# Sound.net
KiCad netlist of a schematic drawn in Altium Designer
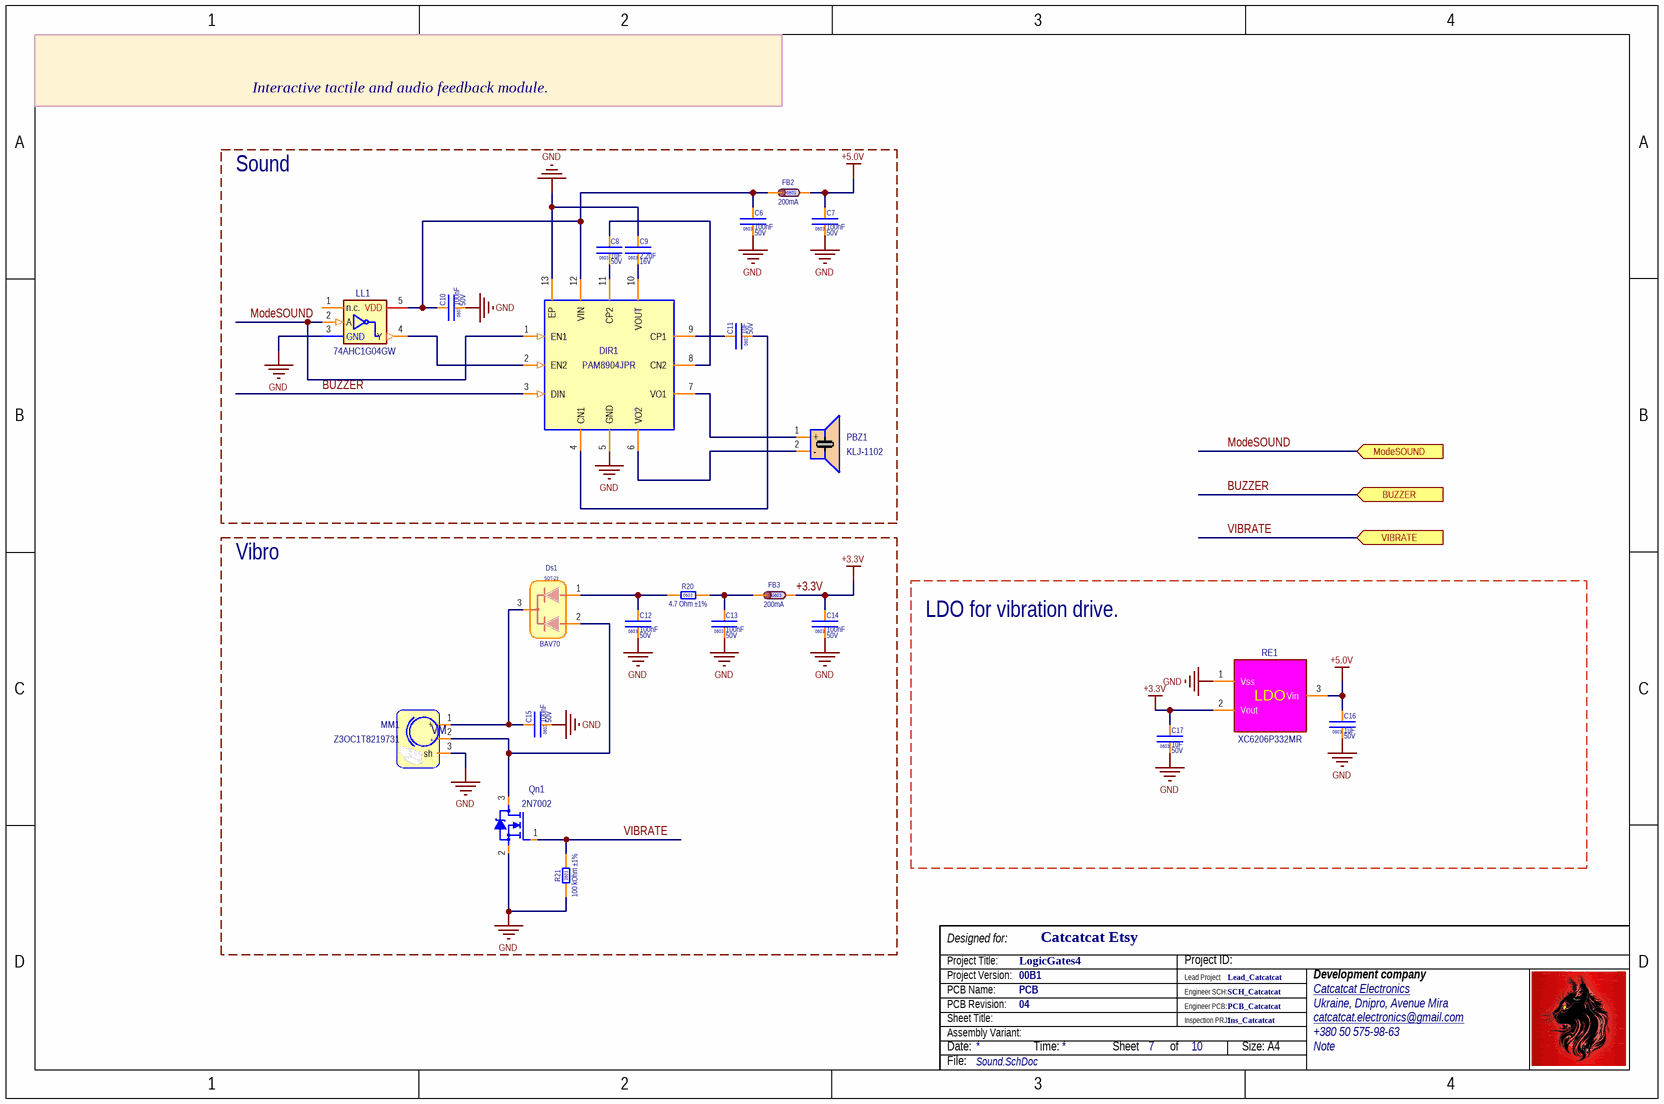
[diagram p0: Sound.SchDoc]

(export (version "E")
  (design (tool "Eeschema 10.0.6"))
  (components
    (comp (ref "C6")
      (value "100nF")
      (footprint "CC0603(1608)x0.8")
      (description "100 nF ±10% 50V X7R")
      (fields
        (field (name "TOLERANCE") "±10%")
        (field (name "VOLTAGE") "50V")
        (field (name "Comment") "100 nF ±10% 50V")
        (field (name "PUBLISHER") "Catcatcat Electronics")
      )
      (libsource (lib "IPC-7351chipCAPC") (part "0603 0.1 uF (B)"))
    )
    (comp (ref "C7")
      (value "100nF")
      (footprint "CC0603(1608)x0.8")
      (description "100 nF ±10% 50V X7R")
      (fields
        (field (name "TOLERANCE") "±10%")
        (field (name "VOLTAGE") "50V")
        (field (name "Comment") "100 nF ±10% 50V")
        (field (name "PUBLISHER") "Catcatcat Electronics")
      )
      (libsource (lib "IPC-7351chipCAPC") (part "0603 0.1 uF (B)"))
    )
    (comp (ref "C8")
      (value "1uF")
      (footprint "CC0603(1608)x0.8")
      (description "1.0 uF ±10% 50V X5R")
      (fields
        (field (name "TOLERANCE") "±10%")
        (field (name "VOLTAGE") "50V")
        (field (name "Comment") "1uF ±10% 50V 0603")
        (field (name "PUBLISHER") "Catcatcat Electronics")
      )
      (libsource (lib "IPC-7351chipCAPC") (part "0603 1.0 uF 50V (B)"))
    )
    (comp (ref "C9")
      (value "2.2uF")
      (footprint "CC0603(1608)x0.8")
      (description "2.2 uF ±10% 16V X5R")
      (fields
        (field (name "TOLERANCE") "±10%")
        (field (name "VOLTAGE") "16V")
        (field (name "Comment") "2.2uF ±10% 16V 0603")
        (field (name "PUBLISHER") "Catcatcat Electronics")
      )
      (libsource (lib "IPC-7351chipCAPC") (part "0603 2.2 uF 16V (B)"))
    )
    (comp (ref "C10")
      (value "100nF")
      (footprint "CC0603(1608)x0.8")
      (description "100 nF ±10% 50V X7R")
      (fields
        (field (name "TOLERANCE") "±10%")
        (field (name "VOLTAGE") "50V")
        (field (name "Comment") "100 nF ±10% 50V")
        (field (name "PUBLISHER") "Catcatcat Electronics")
      )
      (libsource (lib "IPC-7351chipCAPC") (part "0603 0.1 uF (B)"))
    )
    (comp (ref "C11")
      (value "1uF")
      (footprint "CC0603(1608)x0.8")
      (description "1.0 uF ±10% 50V X5R")
      (fields
        (field (name "TOLERANCE") "±10%")
        (field (name "VOLTAGE") "50V")
        (field (name "Comment") "1uF ±10% 50V 0603")
        (field (name "PUBLISHER") "Catcatcat Electronics")
      )
      (libsource (lib "IPC-7351chipCAPC") (part "0603 1.0 uF 50V (B)"))
    )
    (comp (ref "C12")
      (value "100nF")
      (footprint "CC0603(1608)x0.8")
      (description "100 nF ±10% 50V X7R")
      (fields
        (field (name "TOLERANCE") "±10%")
        (field (name "VOLTAGE") "50V")
        (field (name "Comment") "100 nF ±10% 50V")
        (field (name "PUBLISHER") "Catcatcat Electronics")
      )
      (libsource (lib "IPC-7351chipCAPC") (part "0603 0.1 uF (B)"))
    )
    (comp (ref "C13")
      (value "100nF")
      (footprint "CC0603(1608)x0.8")
      (description "100 nF ±10% 50V X7R")
      (fields
        (field (name "TOLERANCE") "±10%")
        (field (name "VOLTAGE") "50V")
        (field (name "Comment") "100 nF ±10% 50V")
        (field (name "PUBLISHER") "Catcatcat Electronics")
      )
      (libsource (lib "IPC-7351chipCAPC") (part "0603 0.1 uF (B)"))
    )
    (comp (ref "C14")
      (value "100nF")
      (footprint "CC0603(1608)x0.8")
      (description "100 nF ±10% 50V X7R")
      (fields
        (field (name "TOLERANCE") "±10%")
        (field (name "VOLTAGE") "50V")
        (field (name "Comment") "100 nF ±10% 50V")
        (field (name "PUBLISHER") "Catcatcat Electronics")
      )
      (libsource (lib "IPC-7351chipCAPC") (part "0603 0.1 uF (B)"))
    )
    (comp (ref "C15")
      (value "100nF")
      (footprint "CC0603(1608)x0.8")
      (description "100 nF ±10% 50V X7R")
      (fields
        (field (name "TOLERANCE") "±10%")
        (field (name "VOLTAGE") "50V")
        (field (name "Comment") "100 nF ±10% 50V")
        (field (name "PUBLISHER") "Catcatcat Electronics")
      )
      (libsource (lib "IPC-7351chipCAPC") (part "0603 0.1 uF (B)"))
    )
    (comp (ref "C16")
      (value "1uF")
      (footprint "CC0603(1608)x0.8")
      (description "1.0 uF ±10% 50V X5R")
      (fields
        (field (name "TOLERANCE") "±10%")
        (field (name "VOLTAGE") "50V")
        (field (name "Comment") "1uF ±10% 50V 0603")
        (field (name "PUBLISHER") "Catcatcat Electronics")
      )
      (libsource (lib "IPC-7351chipCAPC") (part "0603 1.0 uF 50V (B)"))
    )
    (comp (ref "C17")
      (value "1uF")
      (footprint "CC0603(1608)x0.8")
      (description "1.0 uF ±10% 50V X5R")
      (fields
        (field (name "TOLERANCE") "±10%")
        (field (name "VOLTAGE") "50V")
        (field (name "Comment") "1uF ±10% 50V 0603")
        (field (name "PUBLISHER") "Catcatcat Electronics")
      )
      (libsource (lib "IPC-7351chipCAPC") (part "0603 1.0 uF 50V (B)"))
    )
    (comp (ref "DIR1")
      (value "PAM8904JPR")
      (footprint "FP-U-QFN3030-12_Type_B-IPC_C")
      (description "PIEZO SOUNDER DRIVER 18VPP OUTPUT")
      (fields (field (name "VOLTAGE") "1.8V to 5.5V") (field (name "PUBLISHER") "Catcatcat Electronics"))
      (libsource (lib "AudioAmplifier") (part "PAM8904JPR (E)"))
    )
    (comp (ref "Ds1")
      (value "BAV70")
      (footprint "SOT-23 - pdf")
      (description "Switching SOT-23, 200 mA 70 V")
      (fields
        (field (name "VOLTAGE") "70 V")
        (field (name "CASE/PACKAGE") "SOT-23")
        (field (name "PUBLISHER") "Catcatcat Electronics")
      )
      (libsource (lib "Diodes") (part "BAV70 (B)"))
    )
    (comp (ref "FB2")
      (value "200mA")
      (footprint "FB0603(1608)")
      (description "0.20A 600 Ohm @100MHz 450 mOhm")
      (fields (field (name "Comment") "GZ1608D601TF") (field (name "PUBLISHER") "Catcatcat Electronics"))
      (libsource (lib "IPC-7351chipFEB") (part "0603 GZ1608D601TF (B)"))
    )
    (comp (ref "FB3")
      (value "200mA")
      (footprint "FB0603(1608)")
      (description "0.20A 600 Ohm @100MHz 450 mOhm")
      (fields (field (name "Comment") "GZ1608D601TF") (field (name "PUBLISHER") "Catcatcat Electronics"))
      (libsource (lib "IPC-7351chipFEB") (part "0603 GZ1608D601TF (B)"))
    )
    (comp (ref "LL1")
      (value "74AHC1G04GW")
      (footprint "SOT353-5-TSSOP-M")
      (description "IC INVERTER 1CH 1-INP 5TSSOP")
      (fields
        (field (name "VOLTAGE") "2 V ~ 5.5 V")
        (field (name "Comment") "74AHC1G04GW,125")
        (field (name "PUBLISHER") "Catcatcat Electronics")
      )
      (libsource (lib "logic_chip") (part "74AHC1G04GW,125 (E)"))
    )
    (comp (ref "MM1")
      (value "Z3OC1T8219731")
      (footprint "VibrationMotor")
      (description "DC Motor Vibration, ROHS")
      (fields (field (name "VOLTAGE") "2-3.6V") (field (name "PUBLISHER") "Catcatcat Electronics"))
      (libsource (lib "SoundComponents") (part "Z3OC1T8219731 (E)"))
    )
    (comp (ref "PBZ1")
      (value "KLJ-1102")
      (footprint "Cy-SMD-1102-5041")
      (description "Piezoelectric buzzer, Externally Driven 70dB@5V,10cm Externally Driven SMD,9x11mm  Buzzers ROHS")
      (fields (field (name "VOLTAGE") "5V") (field (name "PUBLISHER") "Catcatcat Electronics"))
      (libsource (lib "SoundComponents") (part "KLJ-1102 (E)"))
    )
    (comp (ref "Qn1")
      (value "2N7002")
      (footprint "SOT-23 - pdf")
      (description "N-Channel SOT-23 60V 115mA 200mW 7.5Ω@10V,500mA 2.5V@250uA  SOT-23(SOT-23-3)  MOSFETs ROHS")
      (fields (field (name "VOLTAGE") "60V") (field (name "PUBLISHER") "Catcatcat Electronics"))
      (libsource (lib "Transistors") (part "2N7002 (B)"))
    )
    (comp (ref "R20")
      (value "4.7 Ohm ±1%")
      (footprint "RC0603(1608) -1%")
      (description "4.7 R (4R7) ±1% 1/10W 75V")
      (fields
        (field (name "TOLERANCE") "±1%")
        (field (name "VOLTAGE") "75V")
        (field (name "PUBLISHER") "Catcatcat Electronics")
      )
      (libsource (lib "IPC-7351chipRESC") (part "0603 4.7 Ohm ±1% (B)"))
    )
    (comp (ref "R21")
      (value "100 kOhm ±1%")
      (footprint "RC0603(1608) -1%")
      (description "100 k (104) ±1% 1/10W 50V")
      (fields
        (field (name "TOLERANCE") "±1%")
        (field (name "VOLTAGE") "50V")
        (field (name "PUBLISHER") "Catcatcat Electronics")
      )
      (libsource (lib "IPC-7351chipRESC") (part "0603 100 kOhm ±1% (B)"))
    )
    (comp (ref "RE1")
      (value "XC6206P332MR")
      (footprint "FP-SOT23-IPC_C")
      (description "LDO 5.0V 3.3V 200mA Fixed 3.3V~3.3V Positive 6V SOT-23-3L  Linear Voltage Regulators (LDO) ROHS")
      (fields (field (name "VOLTAGE") "3.3V") (field (name "PUBLISHER") "Catcatcat Electronics"))
      (libsource (lib "Power") (part "XC6206P332MR (B)"))
    )
  )
  (nets
    (net (code "1") (name "+3.3V") (class "Default")
      (node (ref "C14") (pin "2") (pintype "passive"))
      (node (ref "C17") (pin "2") (pintype "passive"))
      (node (ref "FB3") (pin "2") (pintype "passive"))
      (node (ref "RE1") (pin "2") (pinfunction "Vout_2") (pintype "passive"))
    )
    (net (code "2") (name "+5.0V") (class "Default")
      (node (ref "C16") (pin "2") (pintype "passive"))
      (node (ref "C7") (pin "2") (pintype "passive"))
      (node (ref "FB2") (pin "2") (pintype "passive"))
      (node (ref "RE1") (pin "3") (pinfunction "Vin_3") (pintype "passive"))
    )
    (net (code "3") (name "/BUZZER") (class "Default")
      (node (ref "DIR1") (pin "3") (pinfunction "DIN_3") (pintype "input"))
    )
    (net (code "4") (name "/ModeSOUND") (class "Default")
      (node (ref "DIR1") (pin "1") (pinfunction "EN1_1") (pintype "input"))
      (node (ref "LL1") (pin "2") (pinfunction "A_2") (pintype "input"))
    )
    (net (code "5") (name "/VIBRATE") (class "Default")
      (node (ref "Qn1") (pin "1") (pinfunction "G_1") (pintype "passive"))
      (node (ref "R21") (pin "2") (pintype "passive"))
    )
    (net (code "6") (name "GND") (class "Default")
      (node (ref "C10") (pin "1") (pintype "passive"))
      (node (ref "C12") (pin "1") (pintype "passive"))
      (node (ref "C13") (pin "1") (pintype "passive"))
      (node (ref "C14") (pin "1") (pintype "passive"))
      (node (ref "C15") (pin "1") (pintype "passive"))
      (node (ref "C16") (pin "1") (pintype "passive"))
      (node (ref "C17") (pin "1") (pintype "passive"))
      (node (ref "C6") (pin "1") (pintype "passive"))
      (node (ref "C7") (pin "1") (pintype "passive"))
      (node (ref "C9") (pin "2") (pintype "passive"))
      (node (ref "DIR1") (pin "13") (pinfunction "EP_13") (pintype "passive"))
      (node (ref "DIR1") (pin "5") (pinfunction "GND_5") (pintype "power_in"))
      (node (ref "LL1") (pin "3") (pinfunction "GND_3") (pintype "passive"))
      (node (ref "MM1") (pin "3") (pinfunction "sh_3") (pintype "passive"))
      (node (ref "Qn1") (pin "2") (pinfunction "S_2") (pintype "passive"))
      (node (ref "R21") (pin "1") (pintype "passive"))
      (node (ref "RE1") (pin "1") (pinfunction "Vss_1") (pintype "passive"))
    )
    (net (code "7") (name "Net-(C12-Pad2)") (class "Default")
      (node (ref "C12") (pin "2") (pintype "passive"))
      (node (ref "Ds1") (pin "1") (pintype "passive"))
      (node (ref "R20") (pin "1") (pintype "passive"))
    )
    (net (code "8") (name "Net-(C13-Pad2)") (class "Default")
      (node (ref "C13") (pin "2") (pintype "passive"))
      (node (ref "FB3") (pin "1") (pintype "passive"))
      (node (ref "R20") (pin "2") (pintype "passive"))
    )
    (net (code "9") (name "Net-(DIR1-CN1)") (class "Default")
      (node (ref "C11") (pin "1") (pintype "passive"))
      (node (ref "DIR1") (pin "4") (pinfunction "CN1_4") (pintype "passive"))
    )
    (net (code "10") (name "Net-(DIR1-CN2)") (class "Default")
      (node (ref "C8") (pin "2") (pintype "passive"))
      (node (ref "DIR1") (pin "8") (pinfunction "CN2_8") (pintype "passive"))
    )
    (net (code "11") (name "Net-(DIR1-CP1)") (class "Default")
      (node (ref "C11") (pin "2") (pintype "passive"))
      (node (ref "DIR1") (pin "9") (pinfunction "CP1_9") (pintype "passive"))
    )
    (net (code "12") (name "Net-(DIR1-CP2)") (class "Default")
      (node (ref "C8") (pin "1") (pintype "passive"))
      (node (ref "DIR1") (pin "11") (pinfunction "CP2_11") (pintype "passive"))
    )
    (net (code "13") (name "Net-(DIR1-EN2)") (class "Default")
      (node (ref "DIR1") (pin "2") (pinfunction "EN2_2") (pintype "input"))
      (node (ref "LL1") (pin "4") (pinfunction "Y_4") (pintype "output"))
    )
    (net (code "14") (name "Net-(DIR1-VIN)") (class "Default")
      (node (ref "C10") (pin "2") (pintype "passive"))
      (node (ref "C6") (pin "2") (pintype "passive"))
      (node (ref "DIR1") (pin "12") (pinfunction "VIN_12") (pintype "passive"))
      (node (ref "FB2") (pin "1") (pintype "passive"))
      (node (ref "LL1") (pin "5") (pinfunction "VDD_5") (pintype "passive"))
    )
    (net (code "15") (name "Net-(DIR1-VO1)") (class "Default")
      (node (ref "DIR1") (pin "7") (pinfunction "VO1_7") (pintype "passive"))
      (node (ref "PBZ1") (pin "1") (pinfunction "+_1") (pintype "passive"))
    )
    (net (code "16") (name "Net-(DIR1-VO2)") (class "Default")
      (node (ref "DIR1") (pin "6") (pinfunction "VO2_6") (pintype "passive"))
      (node (ref "PBZ1") (pin "2") (pinfunction "-_2") (pintype "passive"))
    )
    (net (code "17") (name "Net-(DIR1-VOUT)") (class "Default")
      (node (ref "C9") (pin "1") (pintype "passive"))
      (node (ref "DIR1") (pin "10") (pinfunction "VOUT_10") (pintype "passive"))
    )
    (net (code "18") (name "Net-(MM1-+)") (class "Default")
      (node (ref "C15") (pin "2") (pintype "passive"))
      (node (ref "Ds1") (pin "3") (pintype "passive"))
      (node (ref "MM1") (pin "1") (pinfunction "+_1") (pintype "passive"))
    )
    (net (code "19") (name "Net-(MM1--)") (class "Default")
      (node (ref "Ds1") (pin "2") (pintype "passive"))
      (node (ref "MM1") (pin "2") (pinfunction "-_2") (pintype "passive"))
      (node (ref "Qn1") (pin "3") (pinfunction "D_3") (pintype "passive"))
    )
    (net (code "20") (name "unconnected-(LL1-n.c.-Pad1)") (class "Default")
      (node (ref "LL1") (pin "1") (pinfunction "n.c._1") (pintype "passive"))
    )
  )
)
